# optoisolator-shield.net
KiCad netlist of a schematic drawn in EAGLE
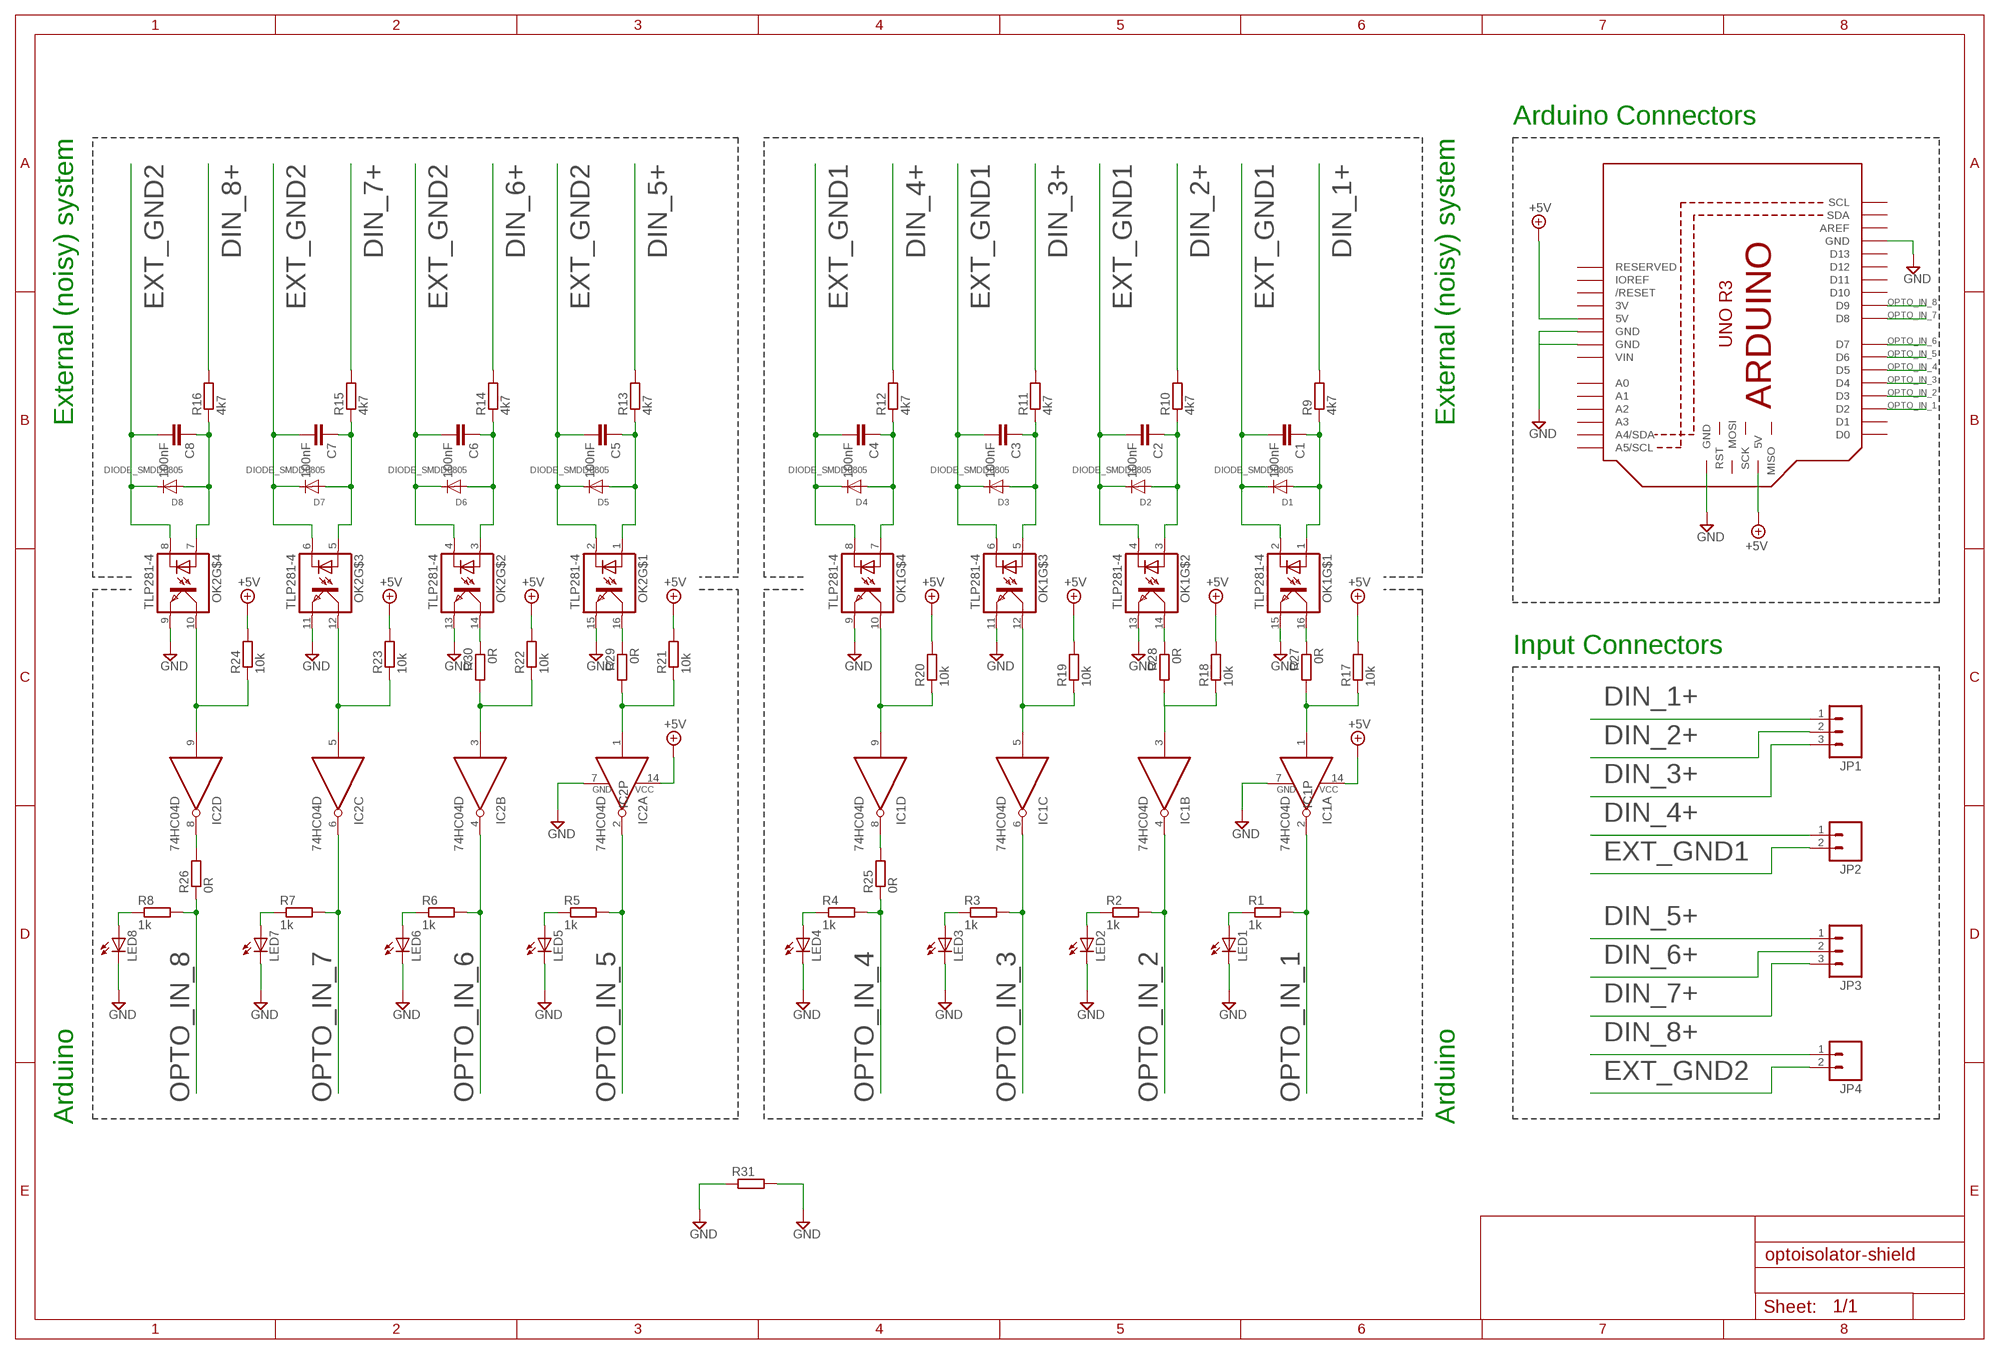
[diagram p0: schematic, sheet 1]

(export (version "E")
  (design (tool "Eeschema 10.0.6"))
  (components
    (comp (ref "C1")
      (value "100nF")
      (footprint "eagle-import:C0603K")
      (libsource (lib "eagle-import") (part "C-EUC0603K"))
    )
    (comp (ref "C2")
      (value "100nF")
      (footprint "eagle-import:C0603K")
      (libsource (lib "eagle-import") (part "C-EUC0603K"))
    )
    (comp (ref "C3")
      (value "100nF")
      (footprint "eagle-import:C0603K")
      (libsource (lib "eagle-import") (part "C-EUC0603K"))
    )
    (comp (ref "C4")
      (value "100nF")
      (footprint "eagle-import:C0603K")
      (libsource (lib "eagle-import") (part "C-EUC0603K"))
    )
    (comp (ref "C5")
      (value "100nF")
      (footprint "eagle-import:C0603K")
      (libsource (lib "eagle-import") (part "C-EUC0603K"))
    )
    (comp (ref "C6")
      (value "100nF")
      (footprint "eagle-import:C0603K")
      (libsource (lib "eagle-import") (part "C-EUC0603K"))
    )
    (comp (ref "C7")
      (value "100nF")
      (footprint "eagle-import:C0603K")
      (libsource (lib "eagle-import") (part "C-EUC0603K"))
    )
    (comp (ref "C8")
      (value "100nF")
      (footprint "eagle-import:C0603K")
      (libsource (lib "eagle-import") (part "C-EUC0603K"))
    )
    (comp (ref "D1")
      (value "DIODE_SMDD0805")
      (footprint "eagle-import:D0805")
      (libsource (lib "eagle-import") (part "DIODE_SMDD0805"))
    )
    (comp (ref "D2")
      (value "DIODE_SMDD0805")
      (footprint "eagle-import:D0805")
      (libsource (lib "eagle-import") (part "DIODE_SMDD0805"))
    )
    (comp (ref "D3")
      (value "DIODE_SMDD0805")
      (footprint "eagle-import:D0805")
      (libsource (lib "eagle-import") (part "DIODE_SMDD0805"))
    )
    (comp (ref "D4")
      (value "DIODE_SMDD0805")
      (footprint "eagle-import:D0805")
      (libsource (lib "eagle-import") (part "DIODE_SMDD0805"))
    )
    (comp (ref "D5")
      (value "DIODE_SMDD0805")
      (footprint "eagle-import:D0805")
      (libsource (lib "eagle-import") (part "DIODE_SMDD0805"))
    )
    (comp (ref "D6")
      (value "DIODE_SMDD0805")
      (footprint "eagle-import:D0805")
      (libsource (lib "eagle-import") (part "DIODE_SMDD0805"))
    )
    (comp (ref "D7")
      (value "DIODE_SMDD0805")
      (footprint "eagle-import:D0805")
      (libsource (lib "eagle-import") (part "DIODE_SMDD0805"))
    )
    (comp (ref "D8")
      (value "DIODE_SMDD0805")
      (footprint "eagle-import:D0805")
      (libsource (lib "eagle-import") (part "DIODE_SMDD0805"))
    )
    (comp (ref "IC1")
      (value "74HC04D")
      (footprint "eagle-import:SO14")
      (libsource (lib "eagle-import") (part "7404DHC"))
    )
    (comp (ref "IC2")
      (value "74HC04D")
      (footprint "eagle-import:SO14")
      (libsource (lib "eagle-import") (part "7404DHC"))
    )
    (comp (ref "JP1")
      (value "M03SCREW_LOCK")
      (footprint "eagle-import:SCREWTERMINAL-3.5MM-3_LOCK.007S")
      (libsource (lib "eagle-import") (part "M03SCREW_LOCK"))
    )
    (comp (ref "JP2")
      (value "M023.5MM")
      (footprint "eagle-import:SCREWTERMINAL-3.5MM-2")
      (libsource (lib "eagle-import") (part "M023.5MM"))
    )
    (comp (ref "JP3")
      (value "M03SCREW_LOCK")
      (footprint "eagle-import:SCREWTERMINAL-3.5MM-3_LOCK.007S")
      (libsource (lib "eagle-import") (part "M03SCREW_LOCK"))
    )
    (comp (ref "JP4")
      (value "M023.5MM")
      (footprint "eagle-import:SCREWTERMINAL-3.5MM-2")
      (libsource (lib "eagle-import") (part "M023.5MM"))
    )
    (comp (ref "LED1")
      (value "LEDSML1206")
      (footprint "eagle-import:SML1206")
      (libsource (lib "eagle-import") (part "LEDSML1206"))
    )
    (comp (ref "LED2")
      (value "LEDSML1206")
      (footprint "eagle-import:SML1206")
      (libsource (lib "eagle-import") (part "LEDSML1206"))
    )
    (comp (ref "LED3")
      (value "LEDSML1206")
      (footprint "eagle-import:SML1206")
      (libsource (lib "eagle-import") (part "LEDSML1206"))
    )
    (comp (ref "LED4")
      (value "LEDSML1206")
      (footprint "eagle-import:SML1206")
      (libsource (lib "eagle-import") (part "LEDSML1206"))
    )
    (comp (ref "LED5")
      (value "LEDSML1206")
      (footprint "eagle-import:SML1206")
      (libsource (lib "eagle-import") (part "LEDSML1206"))
    )
    (comp (ref "LED6")
      (value "LEDSML1206")
      (footprint "eagle-import:SML1206")
      (libsource (lib "eagle-import") (part "LEDSML1206"))
    )
    (comp (ref "LED7")
      (value "LEDSML1206")
      (footprint "eagle-import:SML1206")
      (libsource (lib "eagle-import") (part "LEDSML1206"))
    )
    (comp (ref "LED8")
      (value "LEDSML1206")
      (footprint "eagle-import:SML1206")
      (libsource (lib "eagle-import") (part "LEDSML1206"))
    )
    (comp (ref "M1")
      (value "ARDUINO_R3_ICSP")
      (footprint "eagle-import:ARDUINOR3_ICSP")
      (libsource (lib "eagle-import") (part "ARDUINO_R3_ICSP"))
    )
    (comp (ref "OK1")
      (value "TLP281-4")
      (footprint "eagle-import:MINI-FLAT-16")
      (libsource (lib "eagle-import") (part "TLP281-4"))
    )
    (comp (ref "OK2")
      (value "TLP281-4")
      (footprint "eagle-import:MINI-FLAT-16")
      (libsource (lib "eagle-import") (part "TLP281-4"))
    )
    (comp (ref "R1")
      (value "1k")
      (footprint "eagle-import:R0603")
      (libsource (lib "eagle-import") (part "R-EU_R0603"))
    )
    (comp (ref "R2")
      (value "1k")
      (footprint "eagle-import:R0603")
      (libsource (lib "eagle-import") (part "R-EU_R0603"))
    )
    (comp (ref "R3")
      (value "1k")
      (footprint "eagle-import:R0603")
      (libsource (lib "eagle-import") (part "R-EU_R0603"))
    )
    (comp (ref "R4")
      (value "1k")
      (footprint "eagle-import:R0603")
      (libsource (lib "eagle-import") (part "R-EU_R0603"))
    )
    (comp (ref "R5")
      (value "1k")
      (footprint "eagle-import:R0603")
      (libsource (lib "eagle-import") (part "R-EU_R0603"))
    )
    (comp (ref "R6")
      (value "1k")
      (footprint "eagle-import:R0603")
      (libsource (lib "eagle-import") (part "R-EU_R0603"))
    )
    (comp (ref "R7")
      (value "1k")
      (footprint "eagle-import:R0603")
      (libsource (lib "eagle-import") (part "R-EU_R0603"))
    )
    (comp (ref "R8")
      (value "1k")
      (footprint "eagle-import:R0603")
      (libsource (lib "eagle-import") (part "R-EU_R0603"))
    )
    (comp (ref "R9")
      (value "4k7")
      (footprint "eagle-import:R0603")
      (libsource (lib "eagle-import") (part "R-EU_R0603"))
    )
    (comp (ref "R10")
      (value "4k7")
      (footprint "eagle-import:R0603")
      (libsource (lib "eagle-import") (part "R-EU_R0603"))
    )
    (comp (ref "R11")
      (value "4k7")
      (footprint "eagle-import:R0603")
      (libsource (lib "eagle-import") (part "R-EU_R0603"))
    )
    (comp (ref "R12")
      (value "4k7")
      (footprint "eagle-import:R0603")
      (libsource (lib "eagle-import") (part "R-EU_R0603"))
    )
    (comp (ref "R13")
      (value "4k7")
      (footprint "eagle-import:R0603")
      (libsource (lib "eagle-import") (part "R-EU_R0603"))
    )
    (comp (ref "R14")
      (value "4k7")
      (footprint "eagle-import:R0603")
      (libsource (lib "eagle-import") (part "R-EU_R0603"))
    )
    (comp (ref "R15")
      (value "4k7")
      (footprint "eagle-import:R0603")
      (libsource (lib "eagle-import") (part "R-EU_R0603"))
    )
    (comp (ref "R16")
      (value "4k7")
      (footprint "eagle-import:R0603")
      (libsource (lib "eagle-import") (part "R-EU_R0603"))
    )
    (comp (ref "R17")
      (value "10k")
      (footprint "eagle-import:R0603")
      (libsource (lib "eagle-import") (part "R-EU_R0603"))
    )
    (comp (ref "R18")
      (value "10k")
      (footprint "eagle-import:R0603")
      (libsource (lib "eagle-import") (part "R-EU_R0603"))
    )
    (comp (ref "R19")
      (value "10k")
      (footprint "eagle-import:R0603")
      (libsource (lib "eagle-import") (part "R-EU_R0603"))
    )
    (comp (ref "R20")
      (value "10k")
      (footprint "eagle-import:R0603")
      (libsource (lib "eagle-import") (part "R-EU_R0603"))
    )
    (comp (ref "R21")
      (value "10k")
      (footprint "eagle-import:R0603")
      (libsource (lib "eagle-import") (part "R-EU_R0603"))
    )
    (comp (ref "R22")
      (value "10k")
      (footprint "eagle-import:R0603")
      (libsource (lib "eagle-import") (part "R-EU_R0603"))
    )
    (comp (ref "R23")
      (value "10k")
      (footprint "eagle-import:R0603")
      (libsource (lib "eagle-import") (part "R-EU_R0603"))
    )
    (comp (ref "R24")
      (value "10k")
      (footprint "eagle-import:R0603")
      (libsource (lib "eagle-import") (part "R-EU_R0603"))
    )
    (comp (ref "R25")
      (value "0R")
      (footprint "eagle-import:R2010")
      (libsource (lib "eagle-import") (part "resistor_R-EU_R2010"))
    )
    (comp (ref "R26")
      (value "0R")
      (footprint "eagle-import:R2010")
      (libsource (lib "eagle-import") (part "resistor_R-EU_R2010"))
    )
    (comp (ref "R27")
      (value "0R")
      (footprint "eagle-import:R2010")
      (libsource (lib "eagle-import") (part "resistor_R-EU_R2010"))
    )
    (comp (ref "R28")
      (value "0R")
      (footprint "eagle-import:R2010")
      (libsource (lib "eagle-import") (part "resistor_R-EU_R2010"))
    )
    (comp (ref "R29")
      (value "0R")
      (footprint "eagle-import:R2010")
      (libsource (lib "eagle-import") (part "resistor_R-EU_R2010"))
    )
    (comp (ref "R30")
      (value "0R")
      (footprint "eagle-import:R2010")
      (libsource (lib "eagle-import") (part "resistor_R-EU_R2010"))
    )
    (comp (ref "R31")
      (value "R-EU_R1206")
      (footprint "eagle-import:R1206")
      (libsource (lib "eagle-import") (part "resistor_R-EU_R1206"))
    )
  )
  (nets
    (net (code "1") (name "+5V") (class "Default")
      (node (ref "IC1") (pin "14") (pinfunction "VCC_14") (pintype "power_in"))
      (node (ref "IC2") (pin "14") (pinfunction "VCC_14") (pintype "power_in"))
      (node (ref "M1") (pin "5V") (pinfunction "5V_5V") (pintype "power_in"))
      (node (ref "M1") (pin "5V_ICSP") (pinfunction "5V_5V_ICSP") (pintype "passive"))
      (node (ref "R17") (pin "2") (pinfunction "2_2") (pintype "passive"))
      (node (ref "R18") (pin "2") (pinfunction "2_2") (pintype "passive"))
      (node (ref "R19") (pin "2") (pinfunction "2_2") (pintype "passive"))
      (node (ref "R20") (pin "2") (pinfunction "2_2") (pintype "passive"))
      (node (ref "R21") (pin "2") (pinfunction "2_2") (pintype "passive"))
      (node (ref "R22") (pin "2") (pinfunction "2_2") (pintype "passive"))
      (node (ref "R23") (pin "2") (pinfunction "2_2") (pintype "passive"))
      (node (ref "R24") (pin "2") (pinfunction "2_2") (pintype "passive"))
    )
    (net (code "2") (name "/3V") (class "Default")
      (node (ref "M1") (pin "3V") (pinfunction "3V_3V") (pintype "power_in"))
    )
    (net (code "3") (name "/DIN_1+") (class "Default")
      (node (ref "JP1") (pin "1") (pinfunction "1_1") (pintype "passive"))
      (node (ref "R9") (pin "2") (pinfunction "2_2") (pintype "passive"))
    )
    (net (code "4") (name "/DIN_2+") (class "Default")
      (node (ref "JP1") (pin "2") (pinfunction "2_2") (pintype "passive"))
      (node (ref "R10") (pin "2") (pinfunction "2_2") (pintype "passive"))
    )
    (net (code "5") (name "/DIN_3+") (class "Default")
      (node (ref "JP1") (pin "3") (pinfunction "3_3") (pintype "passive"))
      (node (ref "R11") (pin "2") (pinfunction "2_2") (pintype "passive"))
    )
    (net (code "6") (name "/DIN_4+") (class "Default")
      (node (ref "JP2") (pin "1") (pinfunction "1_1") (pintype "passive"))
      (node (ref "R12") (pin "2") (pinfunction "2_2") (pintype "passive"))
    )
    (net (code "7") (name "/DIN_5+") (class "Default")
      (node (ref "JP3") (pin "1") (pinfunction "1_1") (pintype "passive"))
      (node (ref "R13") (pin "2") (pinfunction "2_2") (pintype "passive"))
    )
    (net (code "8") (name "/DIN_6+") (class "Default")
      (node (ref "JP3") (pin "2") (pinfunction "2_2") (pintype "passive"))
      (node (ref "R14") (pin "2") (pinfunction "2_2") (pintype "passive"))
    )
    (net (code "9") (name "/DIN_7+") (class "Default")
      (node (ref "JP3") (pin "3") (pinfunction "3_3") (pintype "passive"))
      (node (ref "R15") (pin "2") (pinfunction "2_2") (pintype "passive"))
    )
    (net (code "10") (name "/DIN_8+") (class "Default")
      (node (ref "JP4") (pin "1") (pinfunction "1_1") (pintype "passive"))
      (node (ref "R16") (pin "2") (pinfunction "2_2") (pintype "passive"))
    )
    (net (code "11") (name "/EXT_GND1") (class "Default")
      (node (ref "C1") (pin "2") (pinfunction "2_2") (pintype "passive"))
      (node (ref "C2") (pin "2") (pinfunction "2_2") (pintype "passive"))
      (node (ref "C3") (pin "2") (pinfunction "2_2") (pintype "passive"))
      (node (ref "C4") (pin "2") (pinfunction "2_2") (pintype "passive"))
      (node (ref "D1") (pin "K") (pinfunction "K_K") (pintype "bidirectional"))
      (node (ref "D2") (pin "K") (pinfunction "K_K") (pintype "bidirectional"))
      (node (ref "D3") (pin "K") (pinfunction "K_K") (pintype "bidirectional"))
      (node (ref "D4") (pin "K") (pinfunction "K_K") (pintype "bidirectional"))
      (node (ref "JP2") (pin "2") (pinfunction "2_2") (pintype "passive"))
      (node (ref "OK1") (pin "2") (pinfunction "C_2") (pintype "passive"))
      (node (ref "OK1") (pin "4") (pinfunction "C_4") (pintype "passive"))
      (node (ref "OK1") (pin "6") (pinfunction "C_6") (pintype "passive"))
      (node (ref "OK1") (pin "8") (pinfunction "C_8") (pintype "passive"))
    )
    (net (code "12") (name "/EXT_GND2") (class "Default")
      (node (ref "C5") (pin "2") (pinfunction "2_2") (pintype "passive"))
      (node (ref "C6") (pin "2") (pinfunction "2_2") (pintype "passive"))
      (node (ref "C7") (pin "2") (pinfunction "2_2") (pintype "passive"))
      (node (ref "C8") (pin "2") (pinfunction "2_2") (pintype "passive"))
      (node (ref "D5") (pin "K") (pinfunction "K_K") (pintype "bidirectional"))
      (node (ref "D6") (pin "K") (pinfunction "K_K") (pintype "bidirectional"))
      (node (ref "D7") (pin "K") (pinfunction "K_K") (pintype "bidirectional"))
      (node (ref "D8") (pin "K") (pinfunction "K_K") (pintype "bidirectional"))
      (node (ref "JP4") (pin "2") (pinfunction "2_2") (pintype "passive"))
      (node (ref "OK2") (pin "2") (pinfunction "C_2") (pintype "passive"))
      (node (ref "OK2") (pin "4") (pinfunction "C_4") (pintype "passive"))
      (node (ref "OK2") (pin "6") (pinfunction "C_6") (pintype "passive"))
      (node (ref "OK2") (pin "8") (pinfunction "C_8") (pintype "passive"))
    )
    (net (code "13") (name "/OPTO_IN_1") (class "Default")
      (node (ref "IC1") (pin "2") (pinfunction "O_2") (pintype "output"))
      (node (ref "M1") (pin "D2") (pinfunction "D2_D2") (pintype "bidirectional"))
      (node (ref "R1") (pin "2") (pinfunction "2_2") (pintype "passive"))
    )
    (net (code "14") (name "/OPTO_IN_2") (class "Default")
      (node (ref "IC1") (pin "4") (pinfunction "O_4") (pintype "output"))
      (node (ref "M1") (pin "D3") (pinfunction "D3_D3") (pintype "bidirectional"))
      (node (ref "R2") (pin "2") (pinfunction "2_2") (pintype "passive"))
    )
    (net (code "15") (name "/OPTO_IN_3") (class "Default")
      (node (ref "IC1") (pin "6") (pinfunction "O_6") (pintype "output"))
      (node (ref "M1") (pin "D4") (pinfunction "D4_D4") (pintype "bidirectional"))
      (node (ref "R3") (pin "2") (pinfunction "2_2") (pintype "passive"))
    )
    (net (code "16") (name "/OPTO_IN_4") (class "Default")
      (node (ref "M1") (pin "D5") (pinfunction "D5_D5") (pintype "bidirectional"))
      (node (ref "R25") (pin "1") (pinfunction "1_1") (pintype "passive"))
      (node (ref "R4") (pin "2") (pinfunction "2_2") (pintype "passive"))
    )
    (net (code "17") (name "/OPTO_IN_5") (class "Default")
      (node (ref "IC2") (pin "2") (pinfunction "O_2") (pintype "output"))
      (node (ref "M1") (pin "D6") (pinfunction "D6_D6") (pintype "bidirectional"))
      (node (ref "R5") (pin "2") (pinfunction "2_2") (pintype "passive"))
    )
    (net (code "18") (name "/OPTO_IN_6") (class "Default")
      (node (ref "IC2") (pin "4") (pinfunction "O_4") (pintype "output"))
      (node (ref "M1") (pin "D7") (pinfunction "D7_D7") (pintype "bidirectional"))
      (node (ref "R6") (pin "2") (pinfunction "2_2") (pintype "passive"))
    )
    (net (code "19") (name "/OPTO_IN_7") (class "Default")
      (node (ref "IC2") (pin "6") (pinfunction "O_6") (pintype "output"))
      (node (ref "M1") (pin "D8") (pinfunction "D8_D8") (pintype "bidirectional"))
      (node (ref "R7") (pin "2") (pinfunction "2_2") (pintype "passive"))
    )
    (net (code "20") (name "/OPTO_IN_8") (class "Default")
      (node (ref "M1") (pin "D9") (pinfunction "D9_D9") (pintype "bidirectional"))
      (node (ref "R26") (pin "1") (pinfunction "1_1") (pintype "passive"))
      (node (ref "R8") (pin "2") (pinfunction "2_2") (pintype "passive"))
    )
    (net (code "21") (name "/VIN") (class "Default")
      (node (ref "M1") (pin "VIN") (pinfunction "VIN_VIN") (pintype "power_in"))
    )
    (net (code "22") (name "GND") (class "Default")
      (node (ref "IC1") (pin "7") (pinfunction "GND_7") (pintype "power_in"))
      (node (ref "IC2") (pin "7") (pinfunction "GND_7") (pintype "power_in"))
      (node (ref "LED1") (pin "C") (pinfunction "C_C") (pintype "passive"))
      (node (ref "LED2") (pin "C") (pinfunction "C_C") (pintype "passive"))
      (node (ref "LED3") (pin "C") (pinfunction "C_C") (pintype "passive"))
      (node (ref "LED4") (pin "C") (pinfunction "C_C") (pintype "passive"))
      (node (ref "LED5") (pin "C") (pinfunction "C_C") (pintype "passive"))
      (node (ref "LED6") (pin "C") (pinfunction "C_C") (pintype "passive"))
      (node (ref "LED7") (pin "C") (pinfunction "C_C") (pintype "passive"))
      (node (ref "LED8") (pin "C") (pinfunction "C_C") (pintype "passive"))
      (node (ref "M1") (pin "GND") (pinfunction "GND_GND") (pintype "power_in"))
      (node (ref "M1") (pin "GND@1") (pinfunction "GND_GND@1") (pintype "power_in"))
      (node (ref "M1") (pin "GND@2") (pinfunction "GND_GND@2") (pintype "passive"))
      (node (ref "M1") (pin "GND@3") (pinfunction "GND_GND@3") (pintype "power_in"))
      (node (ref "OK1") (pin "11") (pinfunction "EMIT_11") (pintype "passive"))
      (node (ref "OK1") (pin "13") (pinfunction "EMIT_13") (pintype "passive"))
      (node (ref "OK1") (pin "15") (pinfunction "EMIT_15") (pintype "passive"))
      (node (ref "OK1") (pin "9") (pinfunction "EMIT_9") (pintype "passive"))
      (node (ref "OK2") (pin "11") (pinfunction "EMIT_11") (pintype "passive"))
      (node (ref "OK2") (pin "13") (pinfunction "EMIT_13") (pintype "passive"))
      (node (ref "OK2") (pin "15") (pinfunction "EMIT_15") (pintype "passive"))
      (node (ref "OK2") (pin "9") (pinfunction "EMIT_9") (pintype "passive"))
      (node (ref "R31") (pin "1") (pinfunction "1_1") (pintype "passive"))
      (node (ref "R31") (pin "2") (pinfunction "2_2") (pintype "passive"))
    )
    (net (code "23") (name "Net-(IC1A-I)") (class "Default")
      (node (ref "IC1") (pin "1") (pinfunction "I_1") (pintype "input"))
      (node (ref "R17") (pin "1") (pinfunction "1_1") (pintype "passive"))
      (node (ref "R27") (pin "2") (pinfunction "2_2") (pintype "passive"))
    )
    (net (code "24") (name "Net-(IC1B-I)") (class "Default")
      (node (ref "IC1") (pin "3") (pinfunction "I_3") (pintype "input"))
      (node (ref "R18") (pin "1") (pinfunction "1_1") (pintype "passive"))
      (node (ref "R28") (pin "2") (pinfunction "2_2") (pintype "passive"))
    )
    (net (code "25") (name "Net-(IC1C-I)") (class "Default")
      (node (ref "IC1") (pin "5") (pinfunction "I_5") (pintype "input"))
      (node (ref "OK1") (pin "12") (pinfunction "COL_12") (pintype "passive"))
      (node (ref "R19") (pin "1") (pinfunction "1_1") (pintype "passive"))
    )
    (net (code "26") (name "Net-(IC1D-I)") (class "Default")
      (node (ref "IC1") (pin "9") (pinfunction "I_9") (pintype "input"))
      (node (ref "OK1") (pin "10") (pinfunction "COL_10") (pintype "passive"))
      (node (ref "R20") (pin "1") (pinfunction "1_1") (pintype "passive"))
    )
    (net (code "27") (name "Net-(IC1D-O)") (class "Default")
      (node (ref "IC1") (pin "8") (pinfunction "O_8") (pintype "output"))
      (node (ref "R25") (pin "2") (pinfunction "2_2") (pintype "passive"))
    )
    (net (code "28") (name "Net-(IC2A-I)") (class "Default")
      (node (ref "IC2") (pin "1") (pinfunction "I_1") (pintype "input"))
      (node (ref "R21") (pin "1") (pinfunction "1_1") (pintype "passive"))
      (node (ref "R29") (pin "2") (pinfunction "2_2") (pintype "passive"))
    )
    (net (code "29") (name "Net-(IC2B-I)") (class "Default")
      (node (ref "IC2") (pin "3") (pinfunction "I_3") (pintype "input"))
      (node (ref "R22") (pin "1") (pinfunction "1_1") (pintype "passive"))
      (node (ref "R30") (pin "2") (pinfunction "2_2") (pintype "passive"))
    )
    (net (code "30") (name "Net-(IC2C-I)") (class "Default")
      (node (ref "IC2") (pin "5") (pinfunction "I_5") (pintype "input"))
      (node (ref "OK2") (pin "12") (pinfunction "COL_12") (pintype "passive"))
      (node (ref "R23") (pin "1") (pinfunction "1_1") (pintype "passive"))
    )
    (net (code "31") (name "Net-(IC2D-I)") (class "Default")
      (node (ref "IC2") (pin "9") (pinfunction "I_9") (pintype "input"))
      (node (ref "OK2") (pin "10") (pinfunction "COL_10") (pintype "passive"))
      (node (ref "R24") (pin "1") (pinfunction "1_1") (pintype "passive"))
    )
    (net (code "32") (name "Net-(IC2D-O)") (class "Default")
      (node (ref "IC2") (pin "8") (pinfunction "O_8") (pintype "output"))
      (node (ref "R26") (pin "2") (pinfunction "2_2") (pintype "passive"))
    )
    (net (code "33") (name "Net-(LED1-PadA)") (class "Default")
      (node (ref "LED1") (pin "A") (pinfunction "A_A") (pintype "passive"))
      (node (ref "R1") (pin "1") (pinfunction "1_1") (pintype "passive"))
    )
    (net (code "34") (name "Net-(LED2-PadA)") (class "Default")
      (node (ref "LED2") (pin "A") (pinfunction "A_A") (pintype "passive"))
      (node (ref "R2") (pin "1") (pinfunction "1_1") (pintype "passive"))
    )
    (net (code "35") (name "Net-(LED3-PadA)") (class "Default")
      (node (ref "LED3") (pin "A") (pinfunction "A_A") (pintype "passive"))
      (node (ref "R3") (pin "1") (pinfunction "1_1") (pintype "passive"))
    )
    (net (code "36") (name "Net-(LED4-PadA)") (class "Default")
      (node (ref "LED4") (pin "A") (pinfunction "A_A") (pintype "passive"))
      (node (ref "R4") (pin "1") (pinfunction "1_1") (pintype "passive"))
    )
    (net (code "37") (name "Net-(LED5-PadA)") (class "Default")
      (node (ref "LED5") (pin "A") (pinfunction "A_A") (pintype "passive"))
      (node (ref "R5") (pin "1") (pinfunction "1_1") (pintype "passive"))
    )
    (net (code "38") (name "Net-(LED6-PadA)") (class "Default")
      (node (ref "LED6") (pin "A") (pinfunction "A_A") (pintype "passive"))
      (node (ref "R6") (pin "1") (pinfunction "1_1") (pintype "passive"))
    )
    (net (code "39") (name "Net-(LED7-PadA)") (class "Default")
      (node (ref "LED7") (pin "A") (pinfunction "A_A") (pintype "passive"))
      (node (ref "R7") (pin "1") (pinfunction "1_1") (pintype "passive"))
    )
    (net (code "40") (name "Net-(LED8-PadA)") (class "Default")
      (node (ref "LED8") (pin "A") (pinfunction "A_A") (pintype "passive"))
      (node (ref "R8") (pin "1") (pinfunction "1_1") (pintype "passive"))
    )
    (net (code "41") (name "Net-(OK1A-A)") (class "Default")
      (node (ref "C1") (pin "1") (pinfunction "1_1") (pintype "passive"))
      (node (ref "D1") (pin "A") (pinfunction "A_A") (pintype "bidirectional"))
      (node (ref "OK1") (pin "1") (pinfunction "A_1") (pintype "passive"))
      (node (ref "R9") (pin "1") (pinfunction "1_1") (pintype "passive"))
    )
    (net (code "42") (name "Net-(OK1A-COL)") (class "Default")
      (node (ref "OK1") (pin "16") (pinfunction "COL_16") (pintype "passive"))
      (node (ref "R27") (pin "1") (pinfunction "1_1") (pintype "passive"))
    )
    (net (code "43") (name "Net-(OK1B-A)") (class "Default")
      (node (ref "C2") (pin "1") (pinfunction "1_1") (pintype "passive"))
      (node (ref "D2") (pin "A") (pinfunction "A_A") (pintype "bidirectional"))
      (node (ref "OK1") (pin "3") (pinfunction "A_3") (pintype "passive"))
      (node (ref "R10") (pin "1") (pinfunction "1_1") (pintype "passive"))
    )
    (net (code "44") (name "Net-(OK1B-COL)") (class "Default")
      (node (ref "OK1") (pin "14") (pinfunction "COL_14") (pintype "passive"))
      (node (ref "R28") (pin "1") (pinfunction "1_1") (pintype "passive"))
    )
    (net (code "45") (name "Net-(OK1C-A)") (class "Default")
      (node (ref "C3") (pin "1") (pinfunction "1_1") (pintype "passive"))
      (node (ref "D3") (pin "A") (pinfunction "A_A") (pintype "bidirectional"))
      (node (ref "OK1") (pin "5") (pinfunction "A_5") (pintype "passive"))
      (node (ref "R11") (pin "1") (pinfunction "1_1") (pintype "passive"))
    )
    (net (code "46") (name "Net-(OK1D-A)") (class "Default")
      (node (ref "C4") (pin "1") (pinfunction "1_1") (pintype "passive"))
      (node (ref "D4") (pin "A") (pinfunction "A_A") (pintype "bidirectional"))
      (node (ref "OK1") (pin "7") (pinfunction "A_7") (pintype "passive"))
      (node (ref "R12") (pin "1") (pinfunction "1_1") (pintype "passive"))
    )
    (net (code "47") (name "Net-(OK2A-A)") (class "Default")
      (node (ref "C5") (pin "1") (pinfunction "1_1") (pintype "passive"))
      (node (ref "D5") (pin "A") (pinfunction "A_A") (pintype "bidirectional"))
      (node (ref "OK2") (pin "1") (pinfunction "A_1") (pintype "passive"))
      (node (ref "R13") (pin "1") (pinfunction "1_1") (pintype "passive"))
    )
    (net (code "48") (name "Net-(OK2A-COL)") (class "Default")
      (node (ref "OK2") (pin "16") (pinfunction "COL_16") (pintype "passive"))
      (node (ref "R29") (pin "1") (pinfunction "1_1") (pintype "passive"))
    )
    (net (code "49") (name "Net-(OK2B-A)") (class "Default")
      (node (ref "C6") (pin "1") (pinfunction "1_1") (pintype "passive"))
      (node (ref "D6") (pin "A") (pinfunction "A_A") (pintype "bidirectional"))
      (node (ref "OK2") (pin "3") (pinfunction "A_3") (pintype "passive"))
      (node (ref "R14") (pin "1") (pinfunction "1_1") (pintype "passive"))
    )
    (net (code "50") (name "Net-(OK2B-COL)") (class "Default")
      (node (ref "OK2") (pin "14") (pinfunction "COL_14") (pintype "passive"))
      (node (ref "R30") (pin "1") (pinfunction "1_1") (pintype "passive"))
    )
    (net (code "51") (name "Net-(OK2C-A)") (class "Default")
      (node (ref "C7") (pin "1") (pinfunction "1_1") (pintype "passive"))
      (node (ref "D7") (pin "A") (pinfunction "A_A") (pintype "bidirectional"))
      (node (ref "OK2") (pin "5") (pinfunction "A_5") (pintype "passive"))
      (node (ref "R15") (pin "1") (pinfunction "1_1") (pintype "passive"))
    )
    (net (code "52") (name "Net-(OK2D-A)") (class "Default")
      (node (ref "C8") (pin "1") (pinfunction "1_1") (pintype "passive"))
      (node (ref "D8") (pin "A") (pinfunction "A_A") (pintype "bidirectional"))
      (node (ref "OK2") (pin "7") (pinfunction "A_7") (pintype "passive"))
      (node (ref "R16") (pin "1") (pinfunction "1_1") (pintype "passive"))
    )
    (net (code "53") (name "unconnected-(M1-A4{slash}SDA-PadA4)") (class "Default")
      (node (ref "M1") (pin "A4") (pinfunction "A4/SDA_A4") (pintype "bidirectional"))
    )
    (net (code "54") (name "unconnected-(M1-A5{slash}SCL-PadA5)") (class "Default")
      (node (ref "M1") (pin "A5") (pinfunction "A5/SCL_A5") (pintype "bidirectional"))
    )
    (net (code "55") (name "unconnected-(M1-PadA0)") (class "Default")
      (node (ref "M1") (pin "A0") (pinfunction "A0_A0") (pintype "bidirectional"))
    )
    (net (code "56") (name "unconnected-(M1-PadA1)") (class "Default")
      (node (ref "M1") (pin "A1") (pinfunction "A1_A1") (pintype "bidirectional"))
    )
    (net (code "57") (name "unconnected-(M1-PadA2)") (class "Default")
      (node (ref "M1") (pin "A2") (pinfunction "A2_A2") (pintype "bidirectional"))
    )
    (net (code "58") (name "unconnected-(M1-PadA3)") (class "Default")
      (node (ref "M1") (pin "A3") (pinfunction "A3_A3") (pintype "bidirectional"))
    )
    (net (code "59") (name "unconnected-(M1-PadAREF)") (class "Default")
      (node (ref "M1") (pin "AREF") (pinfunction "AREF_AREF") (pintype "bidirectional"))
    )
    (net (code "60") (name "unconnected-(M1-PadD0)") (class "Default")
      (node (ref "M1") (pin "D0") (pinfunction "D0_D0") (pintype "bidirectional"))
    )
    (net (code "61") (name "unconnected-(M1-PadD1)") (class "Default")
      (node (ref "M1") (pin "D1") (pinfunction "D1_D1") (pintype "bidirectional"))
    )
    (net (code "62") (name "unconnected-(M1-PadD10)") (class "Default")
      (node (ref "M1") (pin "D10") (pinfunction "D10_D10") (pintype "bidirectional"))
    )
    (net (code "63") (name "unconnected-(M1-PadD11)") (class "Default")
      (node (ref "M1") (pin "D11") (pinfunction "D11_D11") (pintype "bidirectional"))
    )
    (net (code "64") (name "unconnected-(M1-PadD12)") (class "Default")
      (node (ref "M1") (pin "D12") (pinfunction "D12_D12") (pintype "bidirectional"))
    )
    (net (code "65") (name "unconnected-(M1-PadD13)") (class "Default")
      (node (ref "M1") (pin "D13") (pinfunction "D13_D13") (pintype "bidirectional"))
    )
    (net (code "66") (name "unconnected-(M1-PadIOREF)") (class "Default")
      (node (ref "M1") (pin "IOREF") (pinfunction "IOREF_IOREF") (pintype "output"))
    )
    (net (code "67") (name "unconnected-(M1-PadMISO)") (class "Default")
      (node (ref "M1") (pin "MISO") (pinfunction "MISO_MISO") (pintype "passive"))
    )
    (net (code "68") (name "unconnected-(M1-PadMOSI)") (class "Default")
      (node (ref "M1") (pin "MOSI") (pinfunction "MOSI_MOSI") (pintype "passive"))
    )
    (net (code "69") (name "unconnected-(M1-PadRESERVED)") (class "Default")
      (node (ref "M1") (pin "RESERVED") (pinfunction "RESERVED_RESERVED") (pintype "no_connect"))
    )
    (net (code "70") (name "unconnected-(M1-PadSCK)") (class "Default")
      (node (ref "M1") (pin "SCK") (pinfunction "SCK_SCK") (pintype "passive"))
    )
    (net (code "71") (name "unconnected-(M1-PadSCL)") (class "Default")
      (node (ref "M1") (pin "SCL") (pinfunction "SCL_SCL") (pintype "bidirectional"))
    )
    (net (code "72") (name "unconnected-(M1-PadSDA)") (class "Default")
      (node (ref "M1") (pin "SDA") (pinfunction "SDA_SDA") (pintype "bidirectional"))
    )
    (net (code "73") (name "unconnected-(M1-RST-PadRESET_ICSP)") (class "Default")
      (node (ref "M1") (pin "RESET_ICSP") (pinfunction "RST_RESET_ICSP") (pintype "passive"))
    )
    (net (code "74") (name "unconnected-(M1-{slash}RESET-PadRESET)") (class "Default")
      (node (ref "M1") (pin "RESET") (pinfunction "/RESET_RESET") (pintype "bidirectional"))
    )
  )
)
